# ShifterMatic.net
KiCad netlist of a schematic drawn in Altium Designer
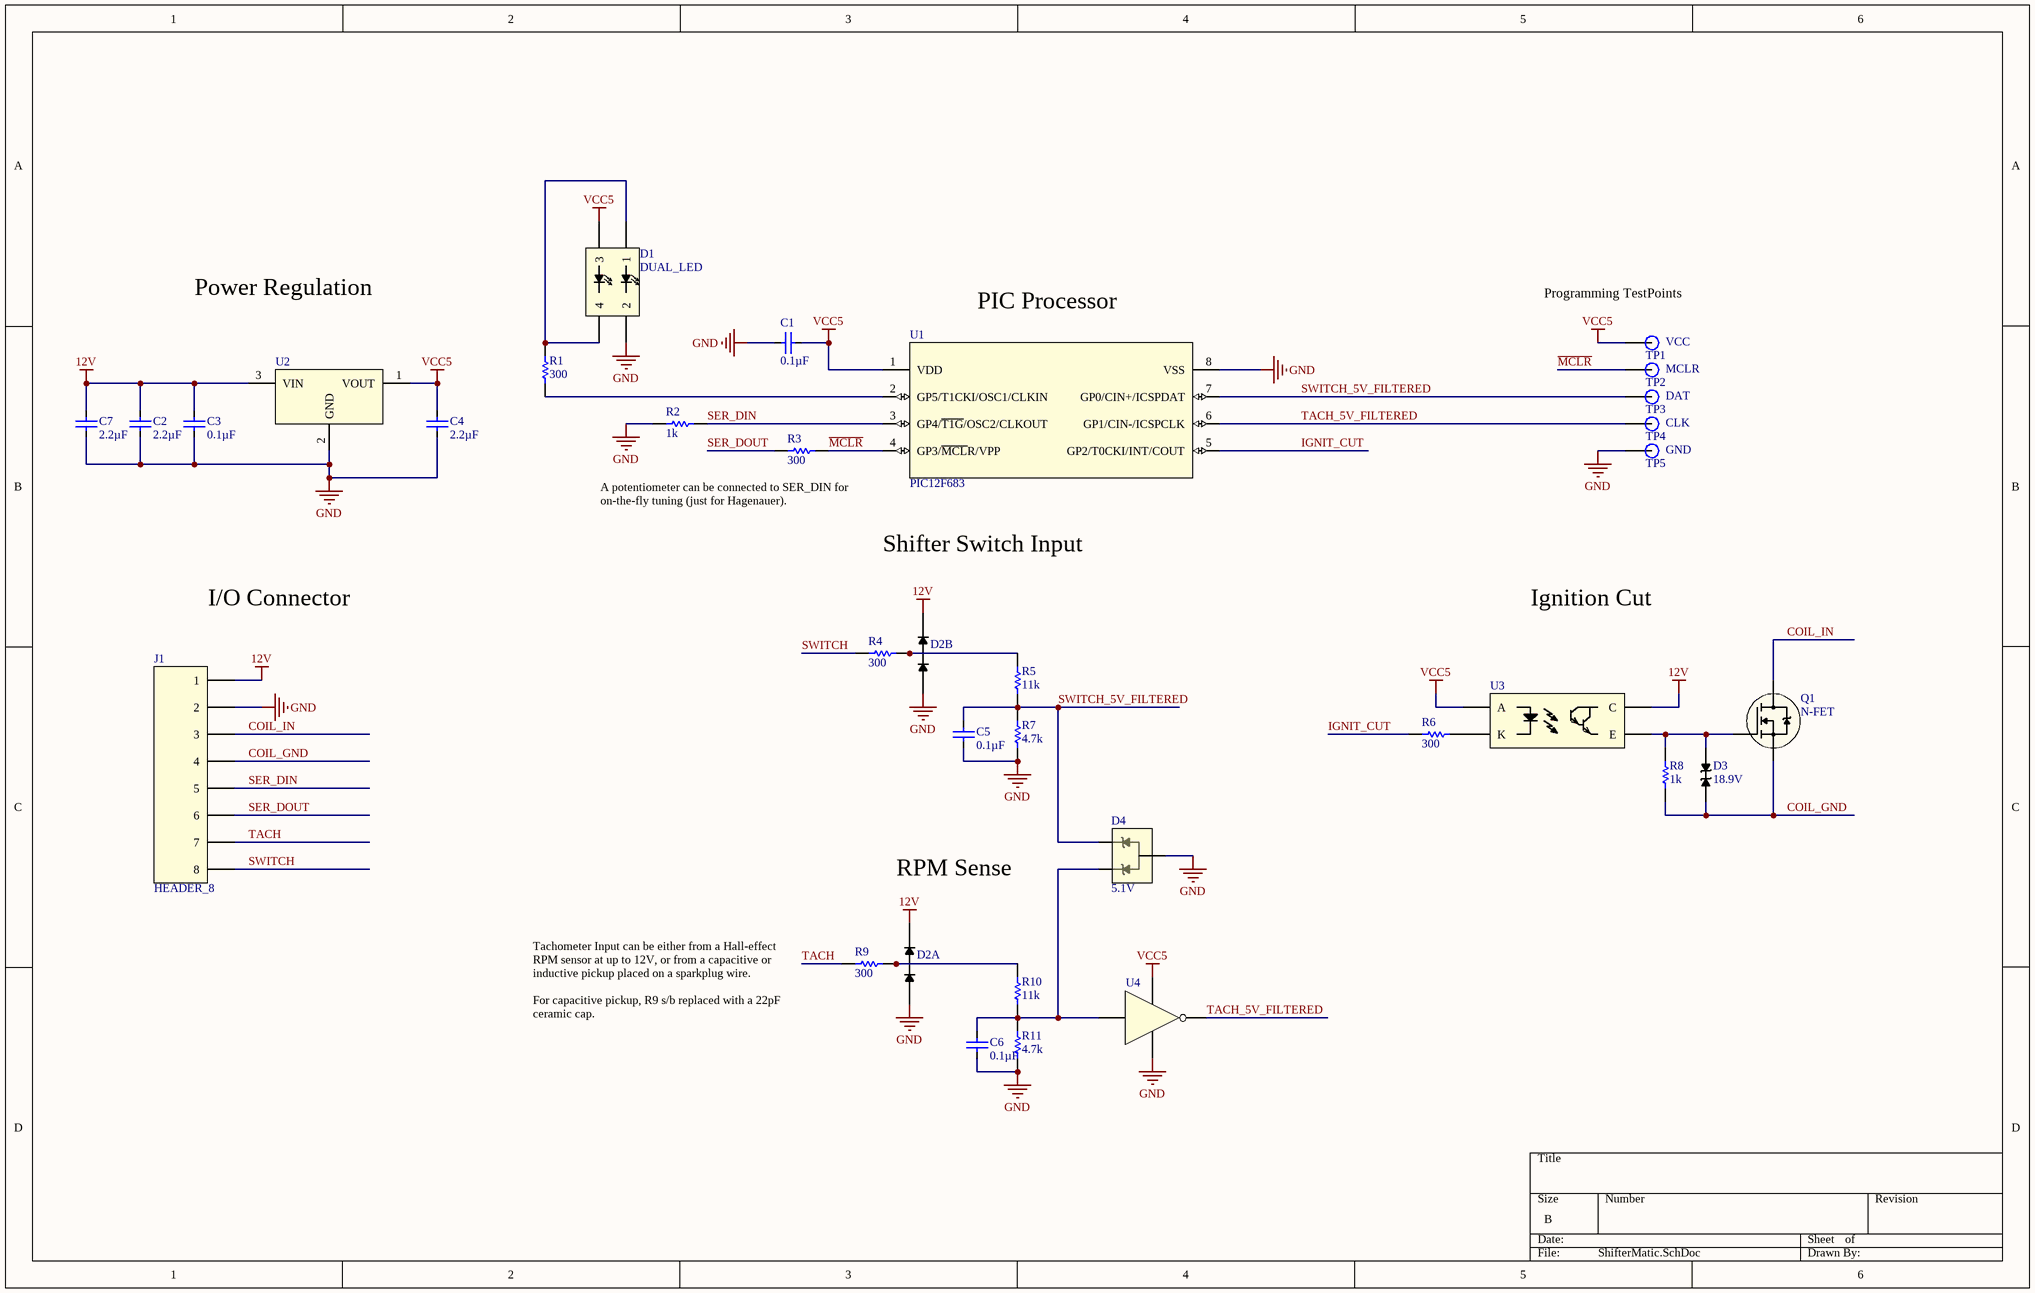
[diagram p0: ShifterMatic.SchDoc]

(export (version "E")
  (design (tool "Eeschema 10.0.6"))
  (components
    (comp (ref "C1")
      (value "0.1µF")
      (footprint "CAP_0603")
      (description "Capacitor")
      (fields (field (name "TOLERANCE") "±10%"))
      (libsource (lib "ShifterMatic") (part "CAPACITOR"))
    )
    (comp (ref "C2")
      (value "2.2µF")
      (footprint "CAP_0805")
      (description "Capacitor")
      (fields (field (name "TOLERANCE") "±20%"))
      (libsource (lib "ShifterMatic") (part "CAPACITOR"))
    )
    (comp (ref "C3")
      (value "0.1µF")
      (footprint "CAP_0603")
      (description "Capacitor")
      (fields (field (name "TOLERANCE") "±10%"))
      (libsource (lib "ShifterMatic") (part "CAPACITOR"))
    )
    (comp (ref "C4")
      (value "2.2µF")
      (footprint "CAP_0805")
      (description "Capacitor")
      (fields (field (name "TOLERANCE") "±20%"))
      (libsource (lib "ShifterMatic") (part "CAPACITOR"))
    )
    (comp (ref "C5")
      (value "0.1µF")
      (footprint "CAP_0603")
      (description "Capacitor")
      (fields (field (name "TOLERANCE") "±10%"))
      (libsource (lib "ShifterMatic") (part "CAPACITOR"))
    )
    (comp (ref "C6")
      (value "0.1µF")
      (footprint "CAP_0603")
      (description "Capacitor")
      (fields (field (name "TOLERANCE") "±10%"))
      (libsource (lib "ShifterMatic") (part "CAPACITOR"))
    )
    (comp (ref "C7")
      (value "2.2µF")
      (footprint "CAP_0805")
      (description "Capacitor")
      (fields (field (name "TOLERANCE") "±20%"))
      (libsource (lib "ShifterMatic") (part "CAPACITOR"))
    )
    (comp (ref "D1")
      (value "DUAL_LED")
      (footprint "KINGBRIGHT_DUAL_SMT_LED")
      (libsource (lib "Shiftermatic") (part "DUAL_LED"))
    )
    (comp (ref "D2")
      (value "DIODE_ARRAY_BAS40BRW")
      (footprint "SOT65P210X110-6N")
      (libsource (lib "Shiftermatic") (part "DIODE_ARRAY_BAS40BRW"))
    )
    (comp (ref "D3")
      (value "18.9V")
      (footprint "DO-214AC_SMA_NONPOLARIZED")
      (libsource (lib "ShifterMatic") (part "TVS_BIDIRECTIONAL"))
    )
    (comp (ref "D4")
      (value "5.1V")
      (footprint "SOT65P210X110-3N")
      (libsource (lib "ShifterMatic") (part "DUAL_ZENER_COM_ANODE"))
    )
    (comp (ref "J1")
      (value "HEADER_8")
      (footprint "MOLEX_MINIFIT_JR_8_PIN")
      (fields
        (field (name "MANUFACTURER PART NUMBER") "0039291088")
        (field (name "MANUFACTURER") "Molex Inc")
      )
      (libsource (lib "Shiftermatic") (part "HEADER_8"))
    )
    (comp (ref "Q1")
      (value "N-FET")
      (footprint "DPAK228P970X238-3N")
      (libsource (lib "Shiftermatic") (part "N-FET"))
    )
    (comp (ref "R1")
      (value "300")
      (footprint "RES_0603")
      (description "=Description")
      (fields (field (name "TOLERANCE") "±5%"))
      (libsource (lib "ShifterMatic") (part "RESISTOR"))
    )
    (comp (ref "R2")
      (value "1k")
      (footprint "RES_0603")
      (description "=Description")
      (fields (field (name "TOLERANCE") "±5%"))
      (libsource (lib "ShifterMatic") (part "RESISTOR"))
    )
    (comp (ref "R3")
      (value "300")
      (footprint "RES_0603")
      (description "=Description")
      (fields (field (name "TOLERANCE") "±5%"))
      (libsource (lib "ShifterMatic") (part "RESISTOR"))
    )
    (comp (ref "R4")
      (value "300")
      (footprint "RES_0603")
      (description "=Description")
      (fields (field (name "TOLERANCE") "±5%"))
      (libsource (lib "ShifterMatic") (part "RESISTOR"))
    )
    (comp (ref "R5")
      (value "11k")
      (footprint "RES_0603")
      (description "=Description")
      (fields (field (name "TOLERANCE") "±5%"))
      (libsource (lib "ShifterMatic") (part "RESISTOR"))
    )
    (comp (ref "R6")
      (value "300")
      (footprint "RES_0603")
      (description "=Description")
      (fields (field (name "TOLERANCE") "±5%"))
      (libsource (lib "ShifterMatic") (part "RESISTOR"))
    )
    (comp (ref "R7")
      (value "4.7k")
      (footprint "RES_0603")
      (description "=Description")
      (fields (field (name "TOLERANCE") "±5%"))
      (libsource (lib "ShifterMatic") (part "RESISTOR"))
    )
    (comp (ref "R8")
      (value "1k")
      (footprint "RES_0603")
      (description "=Description")
      (fields (field (name "TOLERANCE") "±5%"))
      (libsource (lib "ShifterMatic") (part "RESISTOR"))
    )
    (comp (ref "R9")
      (value "300")
      (footprint "RES_0603")
      (description "=Description")
      (fields (field (name "TOLERANCE") "±5%"))
      (libsource (lib "ShifterMatic") (part "RESISTOR"))
    )
    (comp (ref "R10")
      (value "11k")
      (footprint "RES_0603")
      (description "=Description")
      (fields (field (name "TOLERANCE") "±5%"))
      (libsource (lib "ShifterMatic") (part "RESISTOR"))
    )
    (comp (ref "R11")
      (value "4.7k")
      (footprint "RES_0603")
      (description "=Description")
      (fields (field (name "TOLERANCE") "±5%"))
      (libsource (lib "ShifterMatic") (part "RESISTOR"))
    )
    (comp (ref "TP1")
      (value "VCC")
      (footprint "PAD_40MIL")
      (description "Test Point, 40-mil diameter")
      (fields (field (name "PART NUMBER") "TestPoint SMT 40mil"))
      (libsource (lib "AirwareComponents") (part "TestPointPad"))
    )
    (comp (ref "TP2")
      (value "MCLR")
      (footprint "PAD_40MIL")
      (description "Test Point, 40-mil diameter")
      (fields (field (name "PART NUMBER") "TestPoint SMT 40mil"))
      (libsource (lib "AirwareComponents") (part "TestPointPad"))
    )
    (comp (ref "TP3")
      (value "DAT")
      (footprint "PAD_40MIL")
      (description "Test Point, 40-mil diameter")
      (fields (field (name "PART NUMBER") "TestPoint SMT 40mil"))
      (libsource (lib "AirwareComponents") (part "TestPointPad"))
    )
    (comp (ref "TP4")
      (value "CLK")
      (footprint "PAD_40MIL")
      (description "Test Point, 40-mil diameter")
      (fields (field (name "PART NUMBER") "TestPoint SMT 40mil"))
      (libsource (lib "AirwareComponents") (part "TestPointPad"))
    )
    (comp (ref "TP5")
      (value "GND")
      (footprint "PAD_40MIL")
      (description "Test Point, 40-mil diameter")
      (fields (field (name "PART NUMBER") "TestPoint SMT 40mil"))
      (libsource (lib "AirwareComponents") (part "TestPointPad"))
    )
    (comp (ref "U1")
      (value "PIC12F683")
      (footprint "Shiftermatic:SOIC127P600X175-8N")
      (libsource (lib "Shiftermatic") (part "PIC12F675"))
    )
    (comp (ref "U2")
      (value "LDO_NO_ENABLE")
      (footprint "SOT230P700X180-4N")
      (libsource (lib "ShifterMatic") (part "LDO_NO_ENABLE"))
    )
    (comp (ref "U3")
      (value "OPTOISOLATOR_DARLINGTON")
      (footprint "SOP254P680X220-4N")
      (libsource (lib "Shiftermatic") (part "OPTOISOLATOR_DARLINGTON"))
    )
    (comp (ref "U4")
      (value "SCHMITT_TRIGGER")
      (footprint "SOT95P245X110-5N")
      (libsource (lib "Shiftermatic") (part "SCHMITT_TRIGGER"))
    )
  )
  (nets
    (net (code "1") (name "/COIL_GND") (class "Default")
      (node (ref "D3") (pin "1") (pinfunction "1_1") (pintype "power_in"))
      (node (ref "J1") (pin "4") (pinfunction "4_4") (pintype "passive"))
      (node (ref "Q1") (pin "3") (pinfunction "S_3") (pintype "passive"))
      (node (ref "R8") (pin "2") (pinfunction "2_2") (pintype "passive"))
    )
    (net (code "2") (name "/COIL_IN") (class "Default")
      (node (ref "J1") (pin "3") (pinfunction "3_3") (pintype "passive"))
      (node (ref "Q1") (pin "4") (pinfunction "D_4") (pintype "passive"))
    )
    (net (code "3") (name "/IGNIT_CUT") (class "Default")
      (node (ref "R6") (pin "1") (pinfunction "1_1") (pintype "passive"))
      (node (ref "U1") (pin "5") (pinfunction "GP2/T0CKI/INT/COUT_5") (pintype "bidirectional"))
    )
    (net (code "4") (name "/SER_DIN") (class "Default")
      (node (ref "J1") (pin "5") (pinfunction "5_5") (pintype "passive"))
      (node (ref "R2") (pin "1") (pinfunction "1_1") (pintype "passive"))
      (node (ref "U1") (pin "3") (pinfunction "GP4/~{T1G}/OSC2/CLKOUT_3") (pintype "bidirectional"))
    )
    (net (code "5") (name "/SER_DOUT") (class "Default")
      (node (ref "J1") (pin "6") (pinfunction "6_6") (pintype "passive"))
      (node (ref "R3") (pin "1") (pinfunction "1_1") (pintype "passive"))
    )
    (net (code "6") (name "/SWITCH") (class "Default")
      (node (ref "J1") (pin "8") (pinfunction "8_8") (pintype "passive"))
      (node (ref "R4") (pin "1") (pinfunction "1_1") (pintype "passive"))
    )
    (net (code "7") (name "/SWITCH_5V_FILTERED") (class "Default")
      (node (ref "C5") (pin "2") (pinfunction "2_2") (pintype "passive"))
      (node (ref "D4") (pin "1") (pinfunction "C1_1") (pintype "power_in"))
      (node (ref "R5") (pin "1") (pinfunction "1_1") (pintype "passive"))
      (node (ref "R7") (pin "2") (pinfunction "2_2") (pintype "passive"))
      (node (ref "TP3") (pin "1") (pinfunction "1_1") (pintype "passive"))
      (node (ref "U1") (pin "7") (pinfunction "GP0/CIN+/ICSPDAT_7") (pintype "bidirectional"))
    )
    (net (code "8") (name "/TACH") (class "Default")
      (node (ref "J1") (pin "7") (pinfunction "7_7") (pintype "passive"))
      (node (ref "R9") (pin "1") (pinfunction "1_1") (pintype "passive"))
    )
    (net (code "9") (name "/TACH_5V_FILTERED") (class "Default")
      (node (ref "TP4") (pin "1") (pinfunction "1_1") (pintype "passive"))
      (node (ref "U1") (pin "6") (pinfunction "GP1/CIN-/ICSPCLK_6") (pintype "bidirectional"))
      (node (ref "U4") (pin "4") (pinfunction "Y_4") (pintype "passive"))
    )
    (net (code "10") (name "/~{MCLR}") (class "Default")
      (node (ref "R3") (pin "2") (pinfunction "2_2") (pintype "passive"))
      (node (ref "TP2") (pin "1") (pinfunction "1_1") (pintype "passive"))
      (node (ref "U1") (pin "4") (pinfunction "GP3/~{MCL}R/VPP_4") (pintype "bidirectional"))
    )
    (net (code "11") (name "12V") (class "Default")
      (node (ref "C2") (pin "1") (pinfunction "1_1") (pintype "passive"))
      (node (ref "C3") (pin "2") (pinfunction "2_2") (pintype "passive"))
      (node (ref "C7") (pin "1") (pinfunction "1_1") (pintype "passive"))
      (node (ref "D2") (pin "4") (pinfunction "C2_4") (pintype "power_in"))
      (node (ref "D2") (pin "5") (pinfunction "C1_5") (pintype "power_in"))
      (node (ref "J1") (pin "1") (pinfunction "1_1") (pintype "passive"))
      (node (ref "U2") (pin "3") (pinfunction "VIN_3") (pintype "power_in"))
      (node (ref "U3") (pin "4") (pinfunction "C_4") (pintype "passive"))
    )
    (net (code "12") (name "GND") (class "Default")
      (node (ref "C1") (pin "2") (pinfunction "2_2") (pintype "passive"))
      (node (ref "C2") (pin "2") (pinfunction "2_2") (pintype "passive"))
      (node (ref "C3") (pin "1") (pinfunction "1_1") (pintype "passive"))
      (node (ref "C4") (pin "2") (pinfunction "2_2") (pintype "passive"))
      (node (ref "C5") (pin "1") (pinfunction "1_1") (pintype "passive"))
      (node (ref "C6") (pin "1") (pinfunction "1_1") (pintype "passive"))
      (node (ref "C7") (pin "2") (pinfunction "2_2") (pintype "passive"))
      (node (ref "D1") (pin "2") (pinfunction "2_2") (pintype "power_in"))
      (node (ref "D2") (pin "1") (pinfunction "A1_1") (pintype "power_in"))
      (node (ref "D2") (pin "2") (pinfunction "A2_2") (pintype "power_in"))
      (node (ref "D4") (pin "3") (pinfunction "CA_3") (pintype "power_in"))
      (node (ref "J1") (pin "2") (pinfunction "2_2") (pintype "passive"))
      (node (ref "R11") (pin "1") (pinfunction "1_1") (pintype "passive"))
      (node (ref "R2") (pin "2") (pinfunction "2_2") (pintype "passive"))
      (node (ref "R7") (pin "1") (pinfunction "1_1") (pintype "passive"))
      (node (ref "TP5") (pin "1") (pinfunction "1_1") (pintype "passive"))
      (node (ref "U1") (pin "8") (pinfunction "VSS_8") (pintype "power_in"))
      (node (ref "U2") (pin "2") (pinfunction "GND_2") (pintype "power_in"))
      (node (ref "U4") (pin "3") (pinfunction "GND_3") (pintype "power_in"))
    )
    (net (code "13") (name "Net-(D1-Pad1)") (class "Default")
      (node (ref "D1") (pin "1") (pinfunction "1_1") (pintype "power_in"))
      (node (ref "D1") (pin "4") (pinfunction "4_4") (pintype "power_in"))
      (node (ref "R1") (pin "1") (pinfunction "1_1") (pintype "passive"))
    )
    (net (code "14") (name "Net-(D2A-AC1)") (class "Default")
      (node (ref "D2") (pin "6") (pinfunction "AC1_6") (pintype "power_in"))
      (node (ref "R10") (pin "2") (pinfunction "2_2") (pintype "passive"))
      (node (ref "R9") (pin "2") (pinfunction "2_2") (pintype "passive"))
    )
    (net (code "15") (name "Net-(D2B-AC2)") (class "Default")
      (node (ref "D2") (pin "3") (pinfunction "AC2_3") (pintype "power_in"))
      (node (ref "R4") (pin "2") (pinfunction "2_2") (pintype "passive"))
      (node (ref "R5") (pin "2") (pinfunction "2_2") (pintype "passive"))
    )
    (net (code "16") (name "Net-(D4-C2)") (class "Default")
      (node (ref "C6") (pin "2") (pinfunction "2_2") (pintype "passive"))
      (node (ref "D4") (pin "2") (pinfunction "C2_2") (pintype "power_in"))
      (node (ref "R10") (pin "1") (pinfunction "1_1") (pintype "passive"))
      (node (ref "R11") (pin "2") (pinfunction "2_2") (pintype "passive"))
      (node (ref "U4") (pin "2") (pinfunction "A_2") (pintype "passive"))
    )
    (net (code "17") (name "Net-(Q1-G)") (class "Default")
      (node (ref "D3") (pin "2") (pinfunction "2_2") (pintype "power_in"))
      (node (ref "Q1") (pin "1") (pinfunction "G_1") (pintype "passive"))
      (node (ref "R8") (pin "1") (pinfunction "1_1") (pintype "passive"))
      (node (ref "U3") (pin "3") (pinfunction "E_3") (pintype "passive"))
    )
    (net (code "18") (name "Net-(U1-GP5{slash}T1CKI{slash}OSC1{slash}CLKIN)") (class "Default")
      (node (ref "R1") (pin "2") (pinfunction "2_2") (pintype "passive"))
      (node (ref "U1") (pin "2") (pinfunction "GP5/T1CKI/OSC1/CLKIN_2") (pintype "bidirectional"))
    )
    (net (code "19") (name "Net-(U3-K)") (class "Default")
      (node (ref "R6") (pin "2") (pinfunction "2_2") (pintype "passive"))
      (node (ref "U3") (pin "2") (pinfunction "K_2") (pintype "passive"))
    )
    (net (code "20") (name "VCC5") (class "Default")
      (node (ref "C1") (pin "1") (pinfunction "1_1") (pintype "passive"))
      (node (ref "C4") (pin "1") (pinfunction "1_1") (pintype "passive"))
      (node (ref "D1") (pin "3") (pinfunction "3_3") (pintype "power_in"))
      (node (ref "TP1") (pin "1") (pinfunction "1_1") (pintype "passive"))
      (node (ref "U1") (pin "1") (pinfunction "VDD_1") (pintype "power_in"))
      (node (ref "U2") (pin "1") (pinfunction "VOUT_1") (pintype "power_in"))
      (node (ref "U3") (pin "1") (pinfunction "A_1") (pintype "passive"))
      (node (ref "U4") (pin "5") (pinfunction "VCC_5") (pintype "power_in"))
    )
    (net (code "21") (name "unconnected-(U4-NC-Pad1)") (class "Default")
      (node (ref "U4") (pin "1") (pinfunction "NC_1") (pintype "passive"))
    )
  )
)
